# M908X.net
KiCad netlist of a schematic drawn in EAGLE
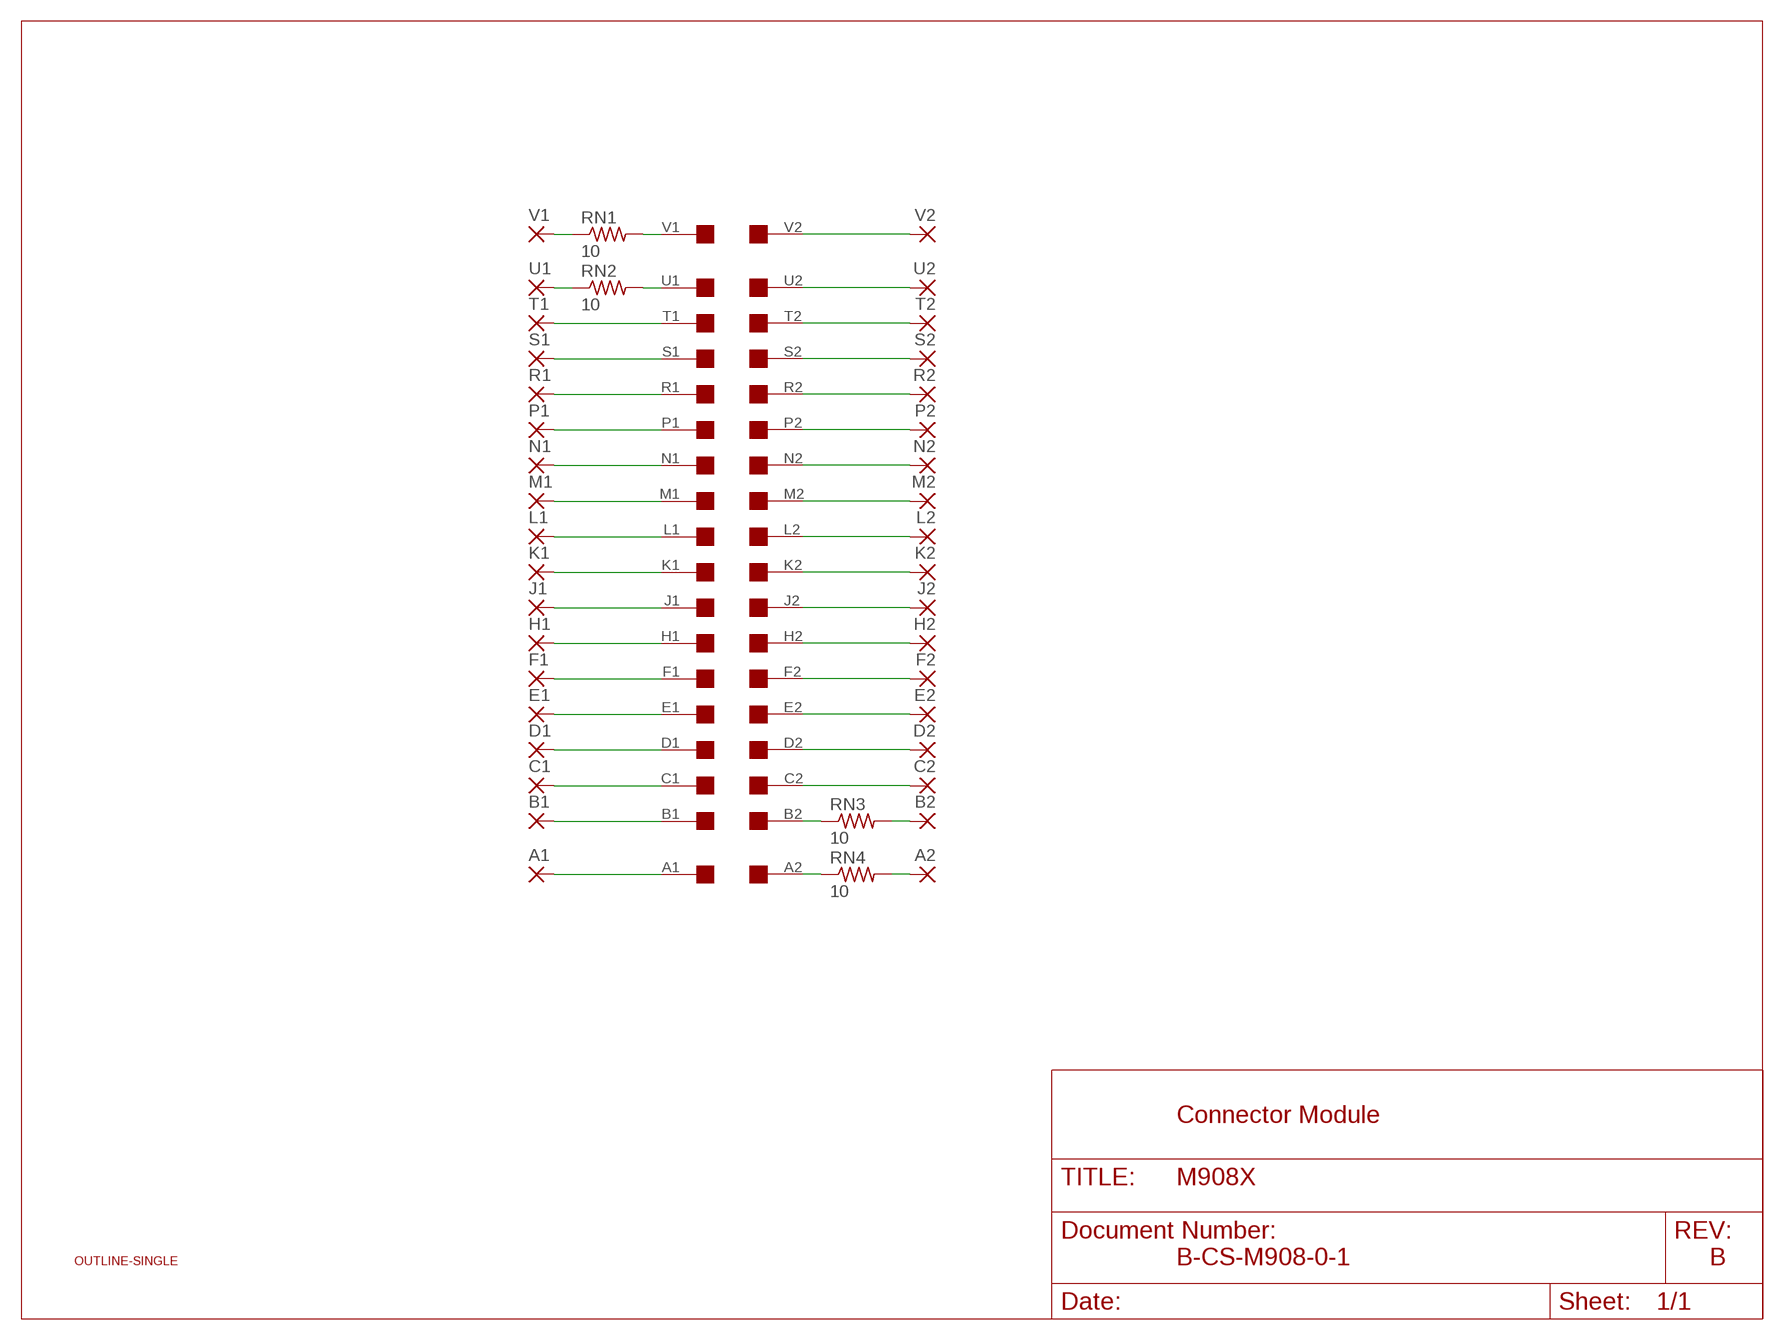
[diagram p0: schematic, sheet 1]

(export (version "E")
  (design (tool "Eeschema 10.0.6"))
  (components
    (comp (ref "A1")
      (value "2,54/1,0")
      (footprint "eagle-import:2,54_1,0")
      (libsource (lib "eagle-import") (part "2,54/1,0"))
    )
    (comp (ref "A2")
      (value "2,54/1,0")
      (footprint "eagle-import:2,54_1,0")
      (libsource (lib "eagle-import") (part "2,54/1,0"))
    )
    (comp (ref "B1")
      (value "2,54/1,0")
      (footprint "eagle-import:2,54_1,0")
      (libsource (lib "eagle-import") (part "2,54/1,0"))
    )
    (comp (ref "B2")
      (value "2,54/1,0")
      (footprint "eagle-import:2,54_1,0")
      (libsource (lib "eagle-import") (part "2,54/1,0"))
    )
    (comp (ref "C1")
      (value "2,54/1,0")
      (footprint "eagle-import:2,54_1,0")
      (libsource (lib "eagle-import") (part "2,54/1,0"))
    )
    (comp (ref "C2")
      (value "2,54/1,0")
      (footprint "eagle-import:2,54_1,0")
      (libsource (lib "eagle-import") (part "2,54/1,0"))
    )
    (comp (ref "D1")
      (value "2,54/1,0")
      (footprint "eagle-import:2,54_1,0")
      (libsource (lib "eagle-import") (part "2,54/1,0"))
    )
    (comp (ref "D2")
      (value "2,54/1,0")
      (footprint "eagle-import:2,54_1,0")
      (libsource (lib "eagle-import") (part "2,54/1,0"))
    )
    (comp (ref "E1")
      (value "2,54/1,0")
      (footprint "eagle-import:2,54_1,0")
      (libsource (lib "eagle-import") (part "2,54/1,0"))
    )
    (comp (ref "E2")
      (value "2,54/1,0")
      (footprint "eagle-import:2,54_1,0")
      (libsource (lib "eagle-import") (part "2,54/1,0"))
    )
    (comp (ref "F1")
      (value "2,54/1,0")
      (footprint "eagle-import:2,54_1,0")
      (libsource (lib "eagle-import") (part "2,54/1,0"))
    )
    (comp (ref "F2")
      (value "2,54/1,0")
      (footprint "eagle-import:2,54_1,0")
      (libsource (lib "eagle-import") (part "2,54/1,0"))
    )
    (comp (ref "H1")
      (value "2,54/1,0")
      (footprint "eagle-import:2,54_1,0")
      (libsource (lib "eagle-import") (part "2,54/1,0"))
    )
    (comp (ref "H2")
      (value "2,54/1,0")
      (footprint "eagle-import:2,54_1,0")
      (libsource (lib "eagle-import") (part "2,54/1,0"))
    )
    (comp (ref "J1")
      (value "2,54/1,0")
      (footprint "eagle-import:2,54_1,0")
      (libsource (lib "eagle-import") (part "2,54/1,0"))
    )
    (comp (ref "J2")
      (value "2,54/1,0")
      (footprint "eagle-import:2,54_1,0")
      (libsource (lib "eagle-import") (part "2,54/1,0"))
    )
    (comp (ref "K1")
      (value "2,54/1,0")
      (footprint "eagle-import:2,54_1,0")
      (libsource (lib "eagle-import") (part "2,54/1,0"))
    )
    (comp (ref "K2")
      (value "2,54/1,0")
      (footprint "eagle-import:2,54_1,0")
      (libsource (lib "eagle-import") (part "2,54/1,0"))
    )
    (comp (ref "L1")
      (value "2,54/1,0")
      (footprint "eagle-import:2,54_1,0")
      (libsource (lib "eagle-import") (part "2,54/1,0"))
    )
    (comp (ref "L2")
      (value "2,54/1,0")
      (footprint "eagle-import:2,54_1,0")
      (libsource (lib "eagle-import") (part "2,54/1,0"))
    )
    (comp (ref "M1")
      (value "2,54/1,0")
      (footprint "eagle-import:2,54_1,0")
      (libsource (lib "eagle-import") (part "2,54/1,0"))
    )
    (comp (ref "M2")
      (value "2,54/1,0")
      (footprint "eagle-import:2,54_1,0")
      (libsource (lib "eagle-import") (part "2,54/1,0"))
    )
    (comp (ref "N1")
      (value "2,54/1,0")
      (footprint "eagle-import:2,54_1,0")
      (libsource (lib "eagle-import") (part "2,54/1,0"))
    )
    (comp (ref "N2")
      (value "2,54/1,0")
      (footprint "eagle-import:2,54_1,0")
      (libsource (lib "eagle-import") (part "2,54/1,0"))
    )
    (comp (ref "P1")
      (value "2,54/1,0")
      (footprint "eagle-import:2,54_1,0")
      (libsource (lib "eagle-import") (part "2,54/1,0"))
    )
    (comp (ref "P2")
      (value "2,54/1,0")
      (footprint "eagle-import:2,54_1,0")
      (libsource (lib "eagle-import") (part "2,54/1,0"))
    )
    (comp (ref "R1")
      (value "2,54/1,0")
      (footprint "eagle-import:2,54_1,0")
      (libsource (lib "eagle-import") (part "2,54/1,0"))
    )
    (comp (ref "R2")
      (value "2,54/1,0")
      (footprint "eagle-import:2,54_1,0")
      (libsource (lib "eagle-import") (part "2,54/1,0"))
    )
    (comp (ref "RN1")
      (value "10")
      (footprint "eagle-import:0207_10")
      (libsource (lib "eagle-import") (part "R-US_0207/10"))
    )
    (comp (ref "RN2")
      (value "10")
      (footprint "eagle-import:0207_10")
      (libsource (lib "eagle-import") (part "R-US_0207/10"))
    )
    (comp (ref "RN3")
      (value "10")
      (footprint "eagle-import:0207_10")
      (libsource (lib "eagle-import") (part "R-US_0207/10"))
    )
    (comp (ref "RN4")
      (value "10")
      (footprint "eagle-import:0207_10")
      (libsource (lib "eagle-import") (part "R-US_0207/10"))
    )
    (comp (ref "S1")
      (value "2,54/1,0")
      (footprint "eagle-import:2,54_1,0")
      (libsource (lib "eagle-import") (part "2,54/1,0"))
    )
    (comp (ref "S2")
      (value "2,54/1,0")
      (footprint "eagle-import:2,54_1,0")
      (libsource (lib "eagle-import") (part "2,54/1,0"))
    )
    (comp (ref "T1")
      (value "2,54/1,0")
      (footprint "eagle-import:2,54_1,0")
      (libsource (lib "eagle-import") (part "2,54/1,0"))
    )
    (comp (ref "T2")
      (value "2,54/1,0")
      (footprint "eagle-import:2,54_1,0")
      (libsource (lib "eagle-import") (part "2,54/1,0"))
    )
    (comp (ref "U$1")
      (value "SINGLE")
      (footprint "eagle-import:EDGE-CON2")
      (libsource (lib "eagle-import") (part "SINGLE"))
    )
    (comp (ref "U$2")
      (value "OUTLINE-SINGLE")
      (footprint "eagle-import:SINGLE")
      (libsource (lib "eagle-import") (part "OUTLINE-SINGLE"))
    )
    (comp (ref "U1")
      (value "2,54/1,0")
      (footprint "eagle-import:2,54_1,0")
      (libsource (lib "eagle-import") (part "2,54/1,0"))
    )
    (comp (ref "U2")
      (value "2,54/1,0")
      (footprint "eagle-import:2,54_1,0")
      (libsource (lib "eagle-import") (part "2,54/1,0"))
    )
    (comp (ref "V1")
      (value "2,54/1,0")
      (footprint "eagle-import:2,54_1,0")
      (libsource (lib "eagle-import") (part "2,54/1,0"))
    )
    (comp (ref "V2")
      (value "2,54/1,0")
      (footprint "eagle-import:2,54_1,0")
      (libsource (lib "eagle-import") (part "2,54/1,0"))
    )
  )
  (nets
    (net (code "1") (name "Net-(A1-P)") (class "Default")
      (node (ref "A1") (pin "1") (pinfunction "P_1") (pintype "passive"))
      (node (ref "U$1") (pin "A1") (pinfunction "1_A1") (pintype "bidirectional"))
    )
    (net (code "2") (name "Net-(A2-P)") (class "Default")
      (node (ref "A2") (pin "1") (pinfunction "P_1") (pintype "passive"))
      (node (ref "RN4") (pin "2") (pinfunction "2_2") (pintype "passive"))
    )
    (net (code "3") (name "Net-(B1-P)") (class "Default")
      (node (ref "B1") (pin "1") (pinfunction "P_1") (pintype "passive"))
      (node (ref "U$1") (pin "B1") (pinfunction "1_B1") (pintype "bidirectional"))
    )
    (net (code "4") (name "Net-(B2-P)") (class "Default")
      (node (ref "B2") (pin "1") (pinfunction "P_1") (pintype "passive"))
      (node (ref "RN3") (pin "2") (pinfunction "2_2") (pintype "passive"))
    )
    (net (code "5") (name "Net-(C1-P)") (class "Default")
      (node (ref "C1") (pin "1") (pinfunction "P_1") (pintype "passive"))
      (node (ref "U$1") (pin "C1") (pinfunction "1_C1") (pintype "bidirectional"))
    )
    (net (code "6") (name "Net-(C2-P)") (class "Default")
      (node (ref "C2") (pin "1") (pinfunction "P_1") (pintype "passive"))
      (node (ref "U$1") (pin "C2") (pinfunction "1_C2") (pintype "bidirectional"))
    )
    (net (code "7") (name "Net-(D1-P)") (class "Default")
      (node (ref "D1") (pin "1") (pinfunction "P_1") (pintype "passive"))
      (node (ref "U$1") (pin "D1") (pinfunction "1_D1") (pintype "bidirectional"))
    )
    (net (code "8") (name "Net-(D2-P)") (class "Default")
      (node (ref "D2") (pin "1") (pinfunction "P_1") (pintype "passive"))
      (node (ref "U$1") (pin "D2") (pinfunction "1_D2") (pintype "bidirectional"))
    )
    (net (code "9") (name "Net-(E1-P)") (class "Default")
      (node (ref "E1") (pin "1") (pinfunction "P_1") (pintype "passive"))
      (node (ref "U$1") (pin "E1") (pinfunction "1_E1") (pintype "bidirectional"))
    )
    (net (code "10") (name "Net-(E2-P)") (class "Default")
      (node (ref "E2") (pin "1") (pinfunction "P_1") (pintype "passive"))
      (node (ref "U$1") (pin "E2") (pinfunction "1_E2") (pintype "bidirectional"))
    )
    (net (code "11") (name "Net-(F1-P)") (class "Default")
      (node (ref "F1") (pin "1") (pinfunction "P_1") (pintype "passive"))
      (node (ref "U$1") (pin "F1") (pinfunction "1_F1") (pintype "bidirectional"))
    )
    (net (code "12") (name "Net-(F2-P)") (class "Default")
      (node (ref "F2") (pin "1") (pinfunction "P_1") (pintype "passive"))
      (node (ref "U$1") (pin "F2") (pinfunction "1_F2") (pintype "bidirectional"))
    )
    (net (code "13") (name "Net-(H1-P)") (class "Default")
      (node (ref "H1") (pin "1") (pinfunction "P_1") (pintype "passive"))
      (node (ref "U$1") (pin "H1") (pinfunction "1_H1") (pintype "bidirectional"))
    )
    (net (code "14") (name "Net-(H2-P)") (class "Default")
      (node (ref "H2") (pin "1") (pinfunction "P_1") (pintype "passive"))
      (node (ref "U$1") (pin "H2") (pinfunction "1_H2") (pintype "bidirectional"))
    )
    (net (code "15") (name "Net-(J1-P)") (class "Default")
      (node (ref "J1") (pin "1") (pinfunction "P_1") (pintype "passive"))
      (node (ref "U$1") (pin "J1") (pinfunction "1_J1") (pintype "bidirectional"))
    )
    (net (code "16") (name "Net-(J2-P)") (class "Default")
      (node (ref "J2") (pin "1") (pinfunction "P_1") (pintype "passive"))
      (node (ref "U$1") (pin "J2") (pinfunction "1_J2") (pintype "bidirectional"))
    )
    (net (code "17") (name "Net-(K1-P)") (class "Default")
      (node (ref "K1") (pin "1") (pinfunction "P_1") (pintype "passive"))
      (node (ref "U$1") (pin "K1") (pinfunction "1_K1") (pintype "bidirectional"))
    )
    (net (code "18") (name "Net-(K2-P)") (class "Default")
      (node (ref "K2") (pin "1") (pinfunction "P_1") (pintype "passive"))
      (node (ref "U$1") (pin "K2") (pinfunction "1_K2") (pintype "bidirectional"))
    )
    (net (code "19") (name "Net-(L1-P)") (class "Default")
      (node (ref "L1") (pin "1") (pinfunction "P_1") (pintype "passive"))
      (node (ref "U$1") (pin "L1") (pinfunction "1_L1") (pintype "bidirectional"))
    )
    (net (code "20") (name "Net-(L2-P)") (class "Default")
      (node (ref "L2") (pin "1") (pinfunction "P_1") (pintype "passive"))
      (node (ref "U$1") (pin "L2") (pinfunction "1_L2") (pintype "bidirectional"))
    )
    (net (code "21") (name "Net-(M1-P)") (class "Default")
      (node (ref "M1") (pin "1") (pinfunction "P_1") (pintype "passive"))
      (node (ref "U$1") (pin "M1") (pinfunction "1_M1") (pintype "bidirectional"))
    )
    (net (code "22") (name "Net-(M2-P)") (class "Default")
      (node (ref "M2") (pin "1") (pinfunction "P_1") (pintype "passive"))
      (node (ref "U$1") (pin "M2") (pinfunction "1_M2") (pintype "bidirectional"))
    )
    (net (code "23") (name "Net-(N1-P)") (class "Default")
      (node (ref "N1") (pin "1") (pinfunction "P_1") (pintype "passive"))
      (node (ref "U$1") (pin "N1") (pinfunction "1_N1") (pintype "bidirectional"))
    )
    (net (code "24") (name "Net-(N2-P)") (class "Default")
      (node (ref "N2") (pin "1") (pinfunction "P_1") (pintype "passive"))
      (node (ref "U$1") (pin "N2") (pinfunction "1_N2") (pintype "bidirectional"))
    )
    (net (code "25") (name "Net-(P1-P)") (class "Default")
      (node (ref "P1") (pin "1") (pinfunction "P_1") (pintype "passive"))
      (node (ref "U$1") (pin "P1") (pinfunction "1_P1") (pintype "bidirectional"))
    )
    (net (code "26") (name "Net-(P2-P)") (class "Default")
      (node (ref "P2") (pin "1") (pinfunction "P_1") (pintype "passive"))
      (node (ref "U$1") (pin "P2") (pinfunction "1_P2") (pintype "bidirectional"))
    )
    (net (code "27") (name "Net-(R1-P)") (class "Default")
      (node (ref "R1") (pin "1") (pinfunction "P_1") (pintype "passive"))
      (node (ref "U$1") (pin "R1") (pinfunction "1_R1") (pintype "bidirectional"))
    )
    (net (code "28") (name "Net-(R2-P)") (class "Default")
      (node (ref "R2") (pin "1") (pinfunction "P_1") (pintype "passive"))
      (node (ref "U$1") (pin "R2") (pinfunction "1_R2") (pintype "bidirectional"))
    )
    (net (code "29") (name "Net-(S1-P)") (class "Default")
      (node (ref "S1") (pin "1") (pinfunction "P_1") (pintype "passive"))
      (node (ref "U$1") (pin "S1") (pinfunction "1_S1") (pintype "bidirectional"))
    )
    (net (code "30") (name "Net-(S2-P)") (class "Default")
      (node (ref "S2") (pin "1") (pinfunction "P_1") (pintype "passive"))
      (node (ref "U$1") (pin "S2") (pinfunction "1_S2") (pintype "bidirectional"))
    )
    (net (code "31") (name "Net-(T1-P)") (class "Default")
      (node (ref "T1") (pin "1") (pinfunction "P_1") (pintype "passive"))
      (node (ref "U$1") (pin "T1") (pinfunction "1_T1") (pintype "bidirectional"))
    )
    (net (code "32") (name "Net-(T2-P)") (class "Default")
      (node (ref "T2") (pin "1") (pinfunction "P_1") (pintype "passive"))
      (node (ref "U$1") (pin "T2") (pinfunction "1_T2") (pintype "bidirectional"))
    )
    (net (code "33") (name "Net-(U$1AG-1)") (class "Default")
      (node (ref "RN2") (pin "2") (pinfunction "2_2") (pintype "passive"))
      (node (ref "U$1") (pin "U1") (pinfunction "1_U1") (pintype "bidirectional"))
    )
    (net (code "34") (name "Net-(U$1AH-1)") (class "Default")
      (node (ref "U$1") (pin "U2") (pinfunction "1_U2") (pintype "bidirectional"))
      (node (ref "U2") (pin "1") (pinfunction "P_1") (pintype "passive"))
    )
    (net (code "35") (name "Net-(U$1AI-1)") (class "Default")
      (node (ref "RN1") (pin "2") (pinfunction "2_2") (pintype "passive"))
      (node (ref "U$1") (pin "V1") (pinfunction "1_V1") (pintype "bidirectional"))
    )
    (net (code "36") (name "Net-(U$1AJ-1)") (class "Default")
      (node (ref "U$1") (pin "V2") (pinfunction "1_V2") (pintype "bidirectional"))
      (node (ref "V2") (pin "1") (pinfunction "P_1") (pintype "passive"))
    )
    (net (code "37") (name "Net-(U$1B-1)") (class "Default")
      (node (ref "RN4") (pin "1") (pinfunction "1_1") (pintype "passive"))
      (node (ref "U$1") (pin "A2") (pinfunction "1_A2") (pintype "bidirectional"))
    )
    (net (code "38") (name "Net-(U$1D-1)") (class "Default")
      (node (ref "RN3") (pin "1") (pinfunction "1_1") (pintype "passive"))
      (node (ref "U$1") (pin "B2") (pinfunction "1_B2") (pintype "bidirectional"))
    )
    (net (code "39") (name "Net-(U1-P)") (class "Default")
      (node (ref "RN2") (pin "1") (pinfunction "1_1") (pintype "passive"))
      (node (ref "U1") (pin "1") (pinfunction "P_1") (pintype "passive"))
    )
    (net (code "40") (name "Net-(V1-P)") (class "Default")
      (node (ref "RN1") (pin "1") (pinfunction "1_1") (pintype "passive"))
      (node (ref "V1") (pin "1") (pinfunction "P_1") (pintype "passive"))
    )
  )
)
